# MINI_SAM_D51_006.net
KiCad netlist of a schematic drawn in EAGLE
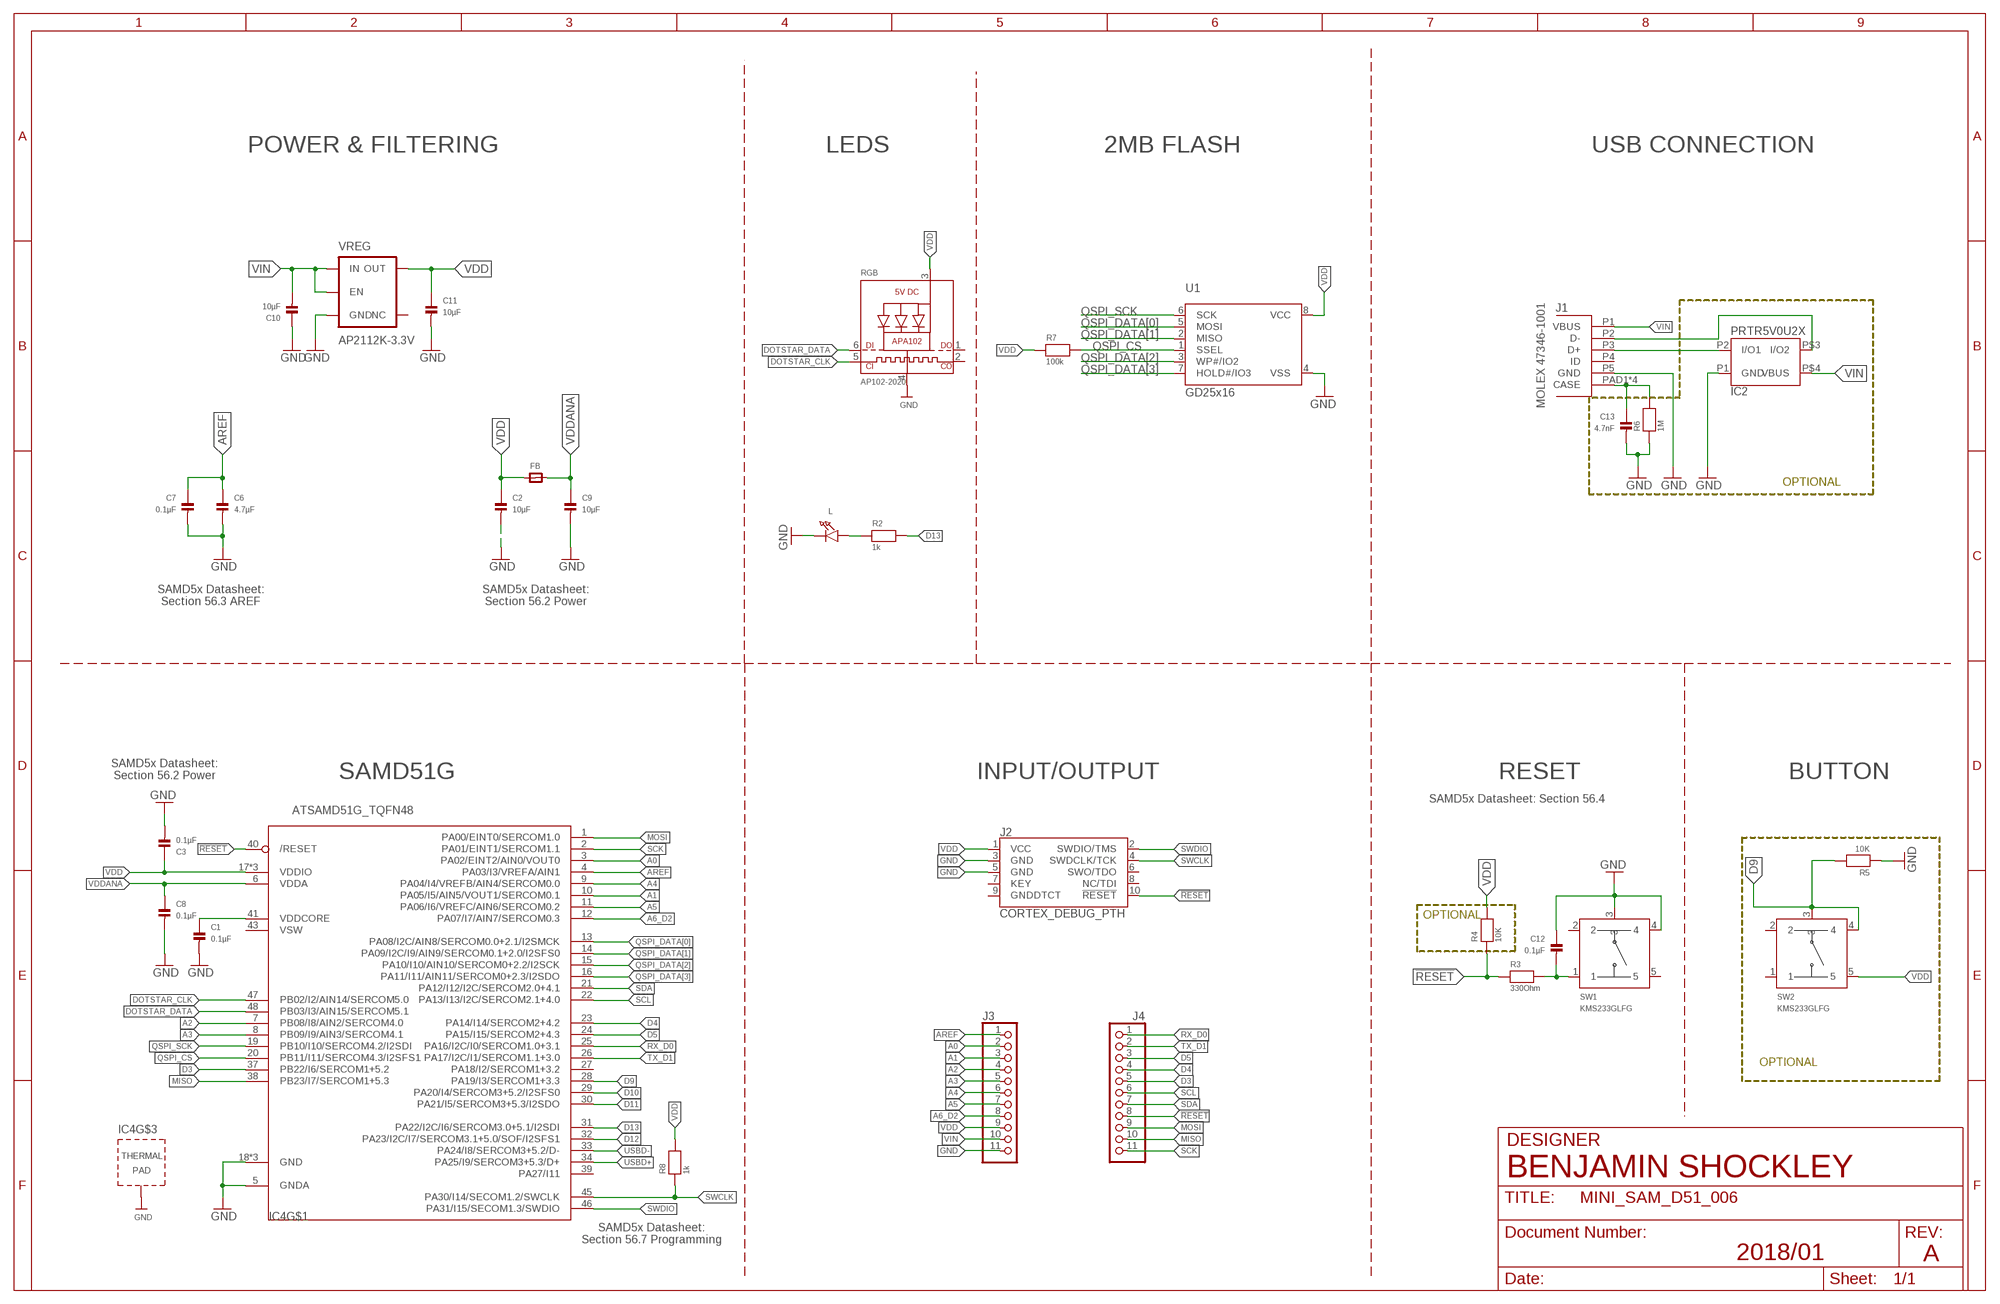
[diagram p0: schematic, sheet 1]

(export (version "E")
  (design (tool "Eeschema 10.0.6"))
  (components
    (comp (ref "C1")
      (value "0.1µF")
      (footprint "eagle-import:_0603MP")
      (libsource (lib "eagle-import") (part "CAP_CERAMIC_0603MP"))
    )
    (comp (ref "C2")
      (value "10µF")
      (footprint "eagle-import:_0603MP")
      (libsource (lib "eagle-import") (part "CAP_CERAMIC_0603MP"))
    )
    (comp (ref "C3")
      (value "0.1µF")
      (footprint "eagle-import:_0603MP")
      (libsource (lib "eagle-import") (part "CAP_CERAMIC_0603MP"))
    )
    (comp (ref "C6")
      (value "4.7µF")
      (footprint "eagle-import:_0603MP")
      (libsource (lib "eagle-import") (part "CAP_CERAMIC_0603MP"))
    )
    (comp (ref "C7")
      (value "0.1µF")
      (footprint "eagle-import:_0603MP")
      (libsource (lib "eagle-import") (part "CAP_CERAMIC_0603MP"))
    )
    (comp (ref "C8")
      (value "0.1µF")
      (footprint "eagle-import:_0603MP")
      (libsource (lib "eagle-import") (part "CAP_CERAMIC_0603MP"))
    )
    (comp (ref "C9")
      (value "10µF")
      (footprint "eagle-import:_0603MP")
      (libsource (lib "eagle-import") (part "CAP_CERAMIC_0603MP"))
    )
    (comp (ref "C10")
      (value "10µF")
      (footprint "eagle-import:_0603MP")
      (libsource (lib "eagle-import") (part "CAP_CERAMIC_0603MP"))
    )
    (comp (ref "C11")
      (value "10µF")
      (footprint "eagle-import:_0603MP")
      (libsource (lib "eagle-import") (part "CAP_CERAMIC_0603MP"))
    )
    (comp (ref "C12")
      (value "0.1µF")
      (footprint "eagle-import:_0603MP")
      (libsource (lib "eagle-import") (part "CAP_CERAMIC_0603MP"))
    )
    (comp (ref "C13")
      (value "4.7nF")
      (footprint "eagle-import:_0603MP")
      (libsource (lib "eagle-import") (part "CAP_CERAMIC_0603MP"))
    )
    (comp (ref "FB")
      (value "FERRITE_0603MP")
      (footprint "eagle-import:_0603MP")
      (libsource (lib "eagle-import") (part "FERRITE_0603MP"))
    )
    (comp (ref "IC2")
      (value "PRTR5V0U2X")
      (footprint "eagle-import:SOT143B_REFLOW")
      (libsource (lib "eagle-import") (part "PRTR5V0U2X"))
    )
    (comp (ref "IC4")
      (value "ATSAMD51G_TQFN48")
      (footprint "eagle-import:TQFN48_7MM")
      (libsource (lib "eagle-import") (part "ATSAMD51G_TQFN48"))
    )
    (comp (ref "J1")
      (value "MOLEX_47346-100147346")
      (footprint "eagle-import:MOLEX_47346-1001")
      (libsource (lib "eagle-import") (part "MOLEX_47346-100147346"))
    )
    (comp (ref "J2")
      (value "CORTEX_DEBUG_PTH")
      (footprint "eagle-import:2X5-PTH-1.27MM")
      (libsource (lib "eagle-import") (part "CORTEX_DEBUG_PTH"))
    )
    (comp (ref "J3")
      (value "PINHD-1X111X11_SMT")
      (footprint "eagle-import:1X11_SMT")
      (libsource (lib "eagle-import") (part "PINHD-1X111X11_SMT"))
    )
    (comp (ref "J4")
      (value "PINHD-1X111X11_SMT")
      (footprint "eagle-import:1X11_SMT")
      (libsource (lib "eagle-import") (part "PINHD-1X111X11_SMT"))
    )
    (comp (ref "L")
      (value "LED0603_NOOUTLINE")
      (footprint "eagle-import:CHIPLED_0603_NOOUTLINE")
      (libsource (lib "eagle-import") (part "LED0603_NOOUTLINE"))
    )
    (comp (ref "R2")
      (value "1k")
      (footprint "eagle-import:_0603MP")
      (libsource (lib "eagle-import") (part "RESISTOR_0603MP"))
    )
    (comp (ref "R3")
      (value "330Ohm")
      (footprint "eagle-import:_0603MP")
      (libsource (lib "eagle-import") (part "RESISTOR_0603MP"))
    )
    (comp (ref "R4")
      (value "10K")
      (footprint "eagle-import:_0603MP")
      (libsource (lib "eagle-import") (part "RESISTOR_0603MP"))
    )
    (comp (ref "R5")
      (value "10K")
      (footprint "eagle-import:_0603MP")
      (libsource (lib "eagle-import") (part "RESISTOR_0603MP"))
    )
    (comp (ref "R6")
      (value "1M")
      (footprint "eagle-import:_0603MP")
      (libsource (lib "eagle-import") (part "RESISTOR_0603MP"))
    )
    (comp (ref "R7")
      (value "100k")
      (footprint "eagle-import:_0603MP")
      (libsource (lib "eagle-import") (part "RESISTOR_0603MP"))
    )
    (comp (ref "R8")
      (value "1k")
      (footprint "eagle-import:_0603MP")
      (libsource (lib "eagle-import") (part "RESISTOR_0603MP"))
    )
    (comp (ref "RGB")
      (value "AP102-2020")
      (footprint "eagle-import:APA102_2020")
      (libsource (lib "eagle-import") (part "APA1022020"))
    )
    (comp (ref "SW1")
      (value "KMS233GLFG")
      (footprint "eagle-import:KMS_SWITCH")
      (libsource (lib "eagle-import") (part "KMS_SWITCHKMS"))
    )
    (comp (ref "SW2")
      (value "KMS233GLFG")
      (footprint "eagle-import:KMS_SWITCH")
      (libsource (lib "eagle-import") (part "KMS_SWITCHKMS"))
    )
    (comp (ref "U1")
      (value "GD25x16")
      (footprint "eagle-import:USON8")
      (libsource (lib "eagle-import") (part "SPIFLASH_8PINUX"))
    )
    (comp (ref "VREG")
      (value "AP2112K-3.3V")
      (footprint "eagle-import:SOT23-5")
      (libsource (lib "eagle-import") (part "V_REG_AP2112K-3.3V"))
    )
  )
  (nets
    (net (code "1") (name "/VSW") (class "Default")
      (node (ref "IC4") (pin "43") (pinfunction "VSW_43") (pintype "power_in"))
    )
    (net (code "2") (name "/~{RESET}") (class "Default")
      (node (ref "IC4") (pin "40") (pinfunction "/RESET_40") (pintype "bidirectional"))
      (node (ref "J2") (pin "10") (pinfunction "~{RESET}_10") (pintype "bidirectional"))
      (node (ref "J4") (pin "8") (pinfunction "8_8") (pintype "passive"))
      (node (ref "R3") (pin "1") (pinfunction "1_1") (pintype "passive"))
      (node (ref "R4") (pin "1") (pinfunction "1_1") (pintype "passive"))
    )
    (net (code "3") (name "A0") (class "Default")
      (node (ref "IC4") (pin "3") (pinfunction "PA02/EINT2/AIN0/VOUT0_3") (pintype "bidirectional"))
      (node (ref "J3") (pin "2") (pinfunction "2_2") (pintype "passive"))
    )
    (net (code "4") (name "A1") (class "Default")
      (node (ref "IC4") (pin "10") (pinfunction "PA05/I5/AIN5/VOUT1/SERCOM0.1_10") (pintype "bidirectional"))
      (node (ref "J3") (pin "3") (pinfunction "3_3") (pintype "passive"))
    )
    (net (code "5") (name "A2") (class "Default")
      (node (ref "IC4") (pin "7") (pinfunction "PB08/I8/AIN2/SERCOM4.0_7") (pintype "bidirectional"))
      (node (ref "J3") (pin "4") (pinfunction "4_4") (pintype "passive"))
    )
    (net (code "6") (name "A3") (class "Default")
      (node (ref "IC4") (pin "8") (pinfunction "PB09/I9/AIN3/SERCOM4.1_8") (pintype "bidirectional"))
      (node (ref "J3") (pin "5") (pinfunction "5_5") (pintype "passive"))
    )
    (net (code "7") (name "A4") (class "Default")
      (node (ref "IC4") (pin "9") (pinfunction "PA04/I4/VREFB/AIN4/SERCOM0.0_9") (pintype "bidirectional"))
      (node (ref "J3") (pin "6") (pinfunction "6_6") (pintype "passive"))
    )
    (net (code "8") (name "A5") (class "Default")
      (node (ref "IC4") (pin "11") (pinfunction "PA06/I6/VREFC/AIN6/SERCOM0.2_11") (pintype "bidirectional"))
      (node (ref "J3") (pin "7") (pinfunction "7_7") (pintype "passive"))
    )
    (net (code "9") (name "A6_D2") (class "Default")
      (node (ref "IC4") (pin "12") (pinfunction "PA07/I7/AIN7/SERCOM0.3_12") (pintype "bidirectional"))
      (node (ref "J3") (pin "8") (pinfunction "8_8") (pintype "passive"))
    )
    (net (code "10") (name "AREF") (class "Default")
      (node (ref "C6") (pin "1") (pinfunction "P$1_1") (pintype "passive"))
      (node (ref "C7") (pin "1") (pinfunction "P$1_1") (pintype "passive"))
      (node (ref "IC4") (pin "4") (pinfunction "PA03/I3/VREFA/AIN1_4") (pintype "bidirectional"))
      (node (ref "J3") (pin "1") (pinfunction "1_1") (pintype "passive"))
    )
    (net (code "11") (name "D3") (class "Default")
      (node (ref "IC4") (pin "37") (pinfunction "PB22/I6/SERCOM1+5.2_37") (pintype "bidirectional"))
      (node (ref "J4") (pin "5") (pinfunction "5_5") (pintype "passive"))
    )
    (net (code "12") (name "D4") (class "Default")
      (node (ref "IC4") (pin "23") (pinfunction "PA14/I14/SERCOM2+4.2_23") (pintype "bidirectional"))
      (node (ref "J4") (pin "4") (pinfunction "4_4") (pintype "passive"))
    )
    (net (code "13") (name "D5") (class "Default")
      (node (ref "IC4") (pin "24") (pinfunction "PA15/I15/SERCOM2+4.3_24") (pintype "bidirectional"))
      (node (ref "J4") (pin "3") (pinfunction "3_3") (pintype "passive"))
    )
    (net (code "14") (name "D9") (class "Default")
      (node (ref "IC4") (pin "28") (pinfunction "PA19/I3/SERCOM1+3.3_28") (pintype "bidirectional"))
      (node (ref "R5") (pin "2") (pinfunction "2_2") (pintype "passive"))
      (node (ref "SW2") (pin "3") (pinfunction "3_3") (pintype "bidirectional"))
      (node (ref "SW2") (pin "4") (pinfunction "4_4") (pintype "bidirectional"))
    )
    (net (code "15") (name "D10") (class "Default")
      (node (ref "IC4") (pin "29") (pinfunction "PA20/I4/SERCOM3+5.2/I2SFS0_29") (pintype "bidirectional"))
    )
    (net (code "16") (name "D11") (class "Default")
      (node (ref "IC4") (pin "30") (pinfunction "PA21/I5/SERCOM3+5.3/I2SDO_30") (pintype "bidirectional"))
    )
    (net (code "17") (name "D12") (class "Default")
      (node (ref "IC4") (pin "32") (pinfunction "PA23/I2C/I7/SERCOM3.1+5.0/SOF/I2SFS1_32") (pintype "bidirectional"))
    )
    (net (code "18") (name "D13") (class "Default")
      (node (ref "IC4") (pin "31") (pinfunction "PA22/I2C/I6/SERCOM3.0+5.1/I2SDI_31") (pintype "bidirectional"))
      (node (ref "R2") (pin "2") (pinfunction "2_2") (pintype "passive"))
    )
    (net (code "19") (name "DOTSTAR_CLK") (class "Default")
      (node (ref "IC4") (pin "47") (pinfunction "PB02/I2/AIN14/SERCOM5.0_47") (pintype "bidirectional"))
      (node (ref "RGB") (pin "5") (pinfunction "CKI_5") (pintype "input"))
    )
    (net (code "20") (name "DOTSTAR_DATA") (class "Default")
      (node (ref "IC4") (pin "48") (pinfunction "PB03/I3/AIN15/SERCOM5.1_48") (pintype "bidirectional"))
      (node (ref "RGB") (pin "6") (pinfunction "DI_6") (pintype "input"))
    )
    (net (code "21") (name "GND") (class "Default")
      (node (ref "C1") (pin "2") (pinfunction "P$2_2") (pintype "passive"))
      (node (ref "C10") (pin "1") (pinfunction "P$1_1") (pintype "passive"))
      (node (ref "C11") (pin "2") (pinfunction "P$2_2") (pintype "passive"))
      (node (ref "C12") (pin "1") (pinfunction "P$1_1") (pintype "passive"))
      (node (ref "C13") (pin "2") (pinfunction "P$2_2") (pintype "passive"))
      (node (ref "C2") (pin "2") (pinfunction "P$2_2") (pintype "passive"))
      (node (ref "C3") (pin "2") (pinfunction "P$2_2") (pintype "passive"))
      (node (ref "C6") (pin "2") (pinfunction "P$2_2") (pintype "passive"))
      (node (ref "C7") (pin "2") (pinfunction "P$2_2") (pintype "passive"))
      (node (ref "C8") (pin "2") (pinfunction "P$2_2") (pintype "passive"))
      (node (ref "C9") (pin "2") (pinfunction "P$2_2") (pintype "passive"))
      (node (ref "IC2") (pin "P1") (pinfunction "GND_P1") (pintype "bidirectional"))
      (node (ref "IC4") (pin "18") (pinfunction "GND_18") (pintype "power_in"))
      (node (ref "IC4") (pin "35") (pinfunction "GND_35") (pintype "power_in"))
      (node (ref "IC4") (pin "42") (pinfunction "GND_42") (pintype "power_in"))
      (node (ref "IC4") (pin "5") (pinfunction "GNDA_5") (pintype "power_in"))
      (node (ref "IC4") (pin "THERMAL") (pinfunction "TP_THERMAL") (pintype "power_in"))
      (node (ref "J1") (pin "P5") (pinfunction "GND_P5") (pintype "power_in"))
      (node (ref "J2") (pin "3") (pinfunction "GND_3") (pintype "bidirectional"))
      (node (ref "J2") (pin "5") (pinfunction "GND_5") (pintype "bidirectional"))
      (node (ref "J3") (pin "11") (pinfunction "11_11") (pintype "passive"))
      (node (ref "L") (pin "C") (pinfunction "C_C") (pintype "passive"))
      (node (ref "R5") (pin "1") (pinfunction "1_1") (pintype "passive"))
      (node (ref "R6") (pin "1") (pinfunction "1_1") (pintype "passive"))
      (node (ref "RGB") (pin "4") (pinfunction "GND_4") (pintype "power_in"))
      (node (ref "SW1") (pin "3") (pinfunction "3_3") (pintype "bidirectional"))
      (node (ref "SW1") (pin "4") (pinfunction "4_4") (pintype "bidirectional"))
      (node (ref "U1") (pin "4") (pinfunction "VSS_4") (pintype "bidirectional"))
      (node (ref "VREG") (pin "2") (pinfunction "GND_2") (pintype "input"))
    )
    (net (code "22") (name "MISO") (class "Default")
      (node (ref "IC4") (pin "38") (pinfunction "PB23/I7/SERCOM1+5.3_38") (pintype "bidirectional"))
      (node (ref "J4") (pin "10") (pinfunction "10_10") (pintype "passive"))
    )
    (net (code "23") (name "MOSI") (class "Default")
      (node (ref "IC4") (pin "1") (pinfunction "PA00/EINT0/SERCOM1.0_1") (pintype "bidirectional"))
      (node (ref "J4") (pin "9") (pinfunction "9_9") (pintype "passive"))
    )
    (net (code "24") (name "Net-(C1-P$1)") (class "Default")
      (node (ref "C1") (pin "1") (pinfunction "P$1_1") (pintype "passive"))
      (node (ref "IC4") (pin "41") (pinfunction "VDDCORE_41") (pintype "power_in"))
    )
    (net (code "25") (name "Net-(C12-P$2)") (class "Default")
      (node (ref "C12") (pin "2") (pinfunction "P$2_2") (pintype "passive"))
      (node (ref "R3") (pin "2") (pinfunction "2_2") (pintype "passive"))
      (node (ref "SW1") (pin "1") (pinfunction "1_1") (pintype "bidirectional"))
    )
    (net (code "26") (name "Net-(C13-P$1)") (class "Default")
      (node (ref "C13") (pin "1") (pinfunction "P$1_1") (pintype "passive"))
      (node (ref "J1") (pin "PAD1") (pinfunction "CASE_PAD1") (pintype "bidirectional"))
      (node (ref "J1") (pin "PAD2") (pinfunction "CASE_PAD2") (pintype "bidirectional"))
      (node (ref "J1") (pin "PAD3") (pinfunction "CASE_PAD3") (pintype "bidirectional"))
      (node (ref "J1") (pin "PAD4") (pinfunction "CASE_PAD4") (pintype "bidirectional"))
      (node (ref "R6") (pin "2") (pinfunction "2_2") (pintype "passive"))
    )
    (net (code "27") (name "Net-(L-PadA)") (class "Default")
      (node (ref "L") (pin "A") (pinfunction "A_A") (pintype "passive"))
      (node (ref "R2") (pin "1") (pinfunction "1_1") (pintype "passive"))
    )
    (net (code "28") (name "QSPI_CS") (class "Default")
      (node (ref "IC4") (pin "20") (pinfunction "PB11/I11/SERCOM4.3/I2SFS1_20") (pintype "bidirectional"))
      (node (ref "R7") (pin "2") (pinfunction "2_2") (pintype "passive"))
      (node (ref "U1") (pin "1") (pinfunction "SSEL_1") (pintype "bidirectional"))
    )
    (net (code "29") (name "QSPI_DATA[0]") (class "Default")
      (node (ref "IC4") (pin "13") (pinfunction "PA08/I2C/AIN8/SERCOM0.0+2.1/I2SMCK_13") (pintype "bidirectional"))
      (node (ref "U1") (pin "5") (pinfunction "MOSI_5") (pintype "bidirectional"))
    )
    (net (code "30") (name "QSPI_DATA[1]") (class "Default")
      (node (ref "IC4") (pin "14") (pinfunction "PA09/I2C/I9/AIN9/SERCOM0.1+2.0/I2SFS0_14") (pintype "bidirectional"))
      (node (ref "U1") (pin "2") (pinfunction "MISO_2") (pintype "bidirectional"))
    )
    (net (code "31") (name "QSPI_DATA[2]") (class "Default")
      (node (ref "IC4") (pin "15") (pinfunction "PA10/I10/AIN10/SERCOM0+2.2/I2SCK_15") (pintype "bidirectional"))
      (node (ref "U1") (pin "3") (pinfunction "WP#/IO2_3") (pintype "bidirectional"))
    )
    (net (code "32") (name "QSPI_DATA[3]") (class "Default")
      (node (ref "IC4") (pin "16") (pinfunction "PA11/I11/AIN11/SERCOM0+2.3/I2SDO_16") (pintype "bidirectional"))
      (node (ref "U1") (pin "7") (pinfunction "HOLD#/IO3_7") (pintype "bidirectional"))
    )
    (net (code "33") (name "QSPI_SCK") (class "Default")
      (node (ref "IC4") (pin "19") (pinfunction "PB10/I10/SERCOM4.2/I2SDI_19") (pintype "bidirectional"))
      (node (ref "U1") (pin "6") (pinfunction "SCK_6") (pintype "bidirectional"))
    )
    (net (code "34") (name "RX_D0") (class "Default")
      (node (ref "IC4") (pin "25") (pinfunction "PA16/I2C/I0/SERCOM1.0+3.1_25") (pintype "bidirectional"))
      (node (ref "J4") (pin "1") (pinfunction "1_1") (pintype "passive"))
    )
    (net (code "35") (name "SCK") (class "Default")
      (node (ref "IC4") (pin "2") (pinfunction "PA01/EINT1/SERCOM1.1_2") (pintype "bidirectional"))
      (node (ref "J4") (pin "11") (pinfunction "11_11") (pintype "passive"))
    )
    (net (code "36") (name "SCL") (class "Default")
      (node (ref "IC4") (pin "22") (pinfunction "PA13/I13/I2C/SERCOM2.1+4.0_22") (pintype "bidirectional"))
      (node (ref "J4") (pin "6") (pinfunction "6_6") (pintype "passive"))
    )
    (net (code "37") (name "SDA") (class "Default")
      (node (ref "IC4") (pin "21") (pinfunction "PA12/I12/I2C/SERCOM2.0+4.1_21") (pintype "bidirectional"))
      (node (ref "J4") (pin "7") (pinfunction "7_7") (pintype "passive"))
    )
    (net (code "38") (name "SWCLK") (class "Default")
      (node (ref "IC4") (pin "45") (pinfunction "PA30/I14/SECOM1.2/SWCLK_45") (pintype "bidirectional"))
      (node (ref "J2") (pin "4") (pinfunction "SWDCLK/TCK_4") (pintype "bidirectional"))
      (node (ref "R8") (pin "1") (pinfunction "1_1") (pintype "passive"))
    )
    (net (code "39") (name "SWDIO") (class "Default")
      (node (ref "IC4") (pin "46") (pinfunction "PA31/I15/SECOM1.3/SWDIO_46") (pintype "bidirectional"))
      (node (ref "J2") (pin "2") (pinfunction "SWDIO/TMS_2") (pintype "bidirectional"))
    )
    (net (code "40") (name "TX_D1") (class "Default")
      (node (ref "IC4") (pin "26") (pinfunction "PA17/I2C/I1/SERCOM1.1+3.0_26") (pintype "bidirectional"))
      (node (ref "J4") (pin "2") (pinfunction "2_2") (pintype "passive"))
    )
    (net (code "41") (name "USBD+") (class "Default")
      (node (ref "IC2") (pin "P2") (pinfunction "I/O1_P2") (pintype "bidirectional"))
      (node (ref "IC4") (pin "34") (pinfunction "PA25/I9/SERCOM3+5.3/D+_34") (pintype "bidirectional"))
      (node (ref "J1") (pin "P3") (pinfunction "D+_P3") (pintype "bidirectional"))
    )
    (net (code "42") (name "USBD-") (class "Default")
      (node (ref "IC2") (pin "P$3") (pinfunction "I/O2_P$3") (pintype "bidirectional"))
      (node (ref "IC4") (pin "33") (pinfunction "PA24/I8/SERCOM3+5.2/D-_33") (pintype "bidirectional"))
      (node (ref "J1") (pin "P2") (pinfunction "D-_P2") (pintype "bidirectional"))
    )
    (net (code "43") (name "VDD") (class "Default")
      (node (ref "C11") (pin "1") (pinfunction "P$1_1") (pintype "passive"))
      (node (ref "C2") (pin "1") (pinfunction "P$1_1") (pintype "passive"))
      (node (ref "C3") (pin "1") (pinfunction "P$1_1") (pintype "passive"))
      (node (ref "FB") (pin "1") (pinfunction "P$1_1") (pintype "passive"))
      (node (ref "IC4") (pin "17") (pinfunction "VDDIO_17") (pintype "power_in"))
      (node (ref "IC4") (pin "36") (pinfunction "VDDIO_36") (pintype "power_in"))
      (node (ref "IC4") (pin "44") (pinfunction "VDDIO_44") (pintype "power_in"))
      (node (ref "J2") (pin "1") (pinfunction "VCC_1") (pintype "bidirectional"))
      (node (ref "J3") (pin "9") (pinfunction "9_9") (pintype "passive"))
      (node (ref "R4") (pin "2") (pinfunction "2_2") (pintype "passive"))
      (node (ref "R7") (pin "1") (pinfunction "1_1") (pintype "passive"))
      (node (ref "R8") (pin "2") (pinfunction "2_2") (pintype "passive"))
      (node (ref "RGB") (pin "3") (pinfunction "VDD_3") (pintype "power_in"))
      (node (ref "SW2") (pin "5") (pinfunction "5_5") (pintype "bidirectional"))
      (node (ref "U1") (pin "8") (pinfunction "VCC_8") (pintype "bidirectional"))
      (node (ref "VREG") (pin "5") (pinfunction "OUT_5") (pintype "passive"))
    )
    (net (code "44") (name "VDDANA") (class "Default")
      (node (ref "C8") (pin "1") (pinfunction "P$1_1") (pintype "passive"))
      (node (ref "C9") (pin "1") (pinfunction "P$1_1") (pintype "passive"))
      (node (ref "FB") (pin "2") (pinfunction "P$2_2") (pintype "passive"))
      (node (ref "IC4") (pin "6") (pinfunction "VDDA_6") (pintype "power_in"))
    )
    (net (code "45") (name "VIN") (class "Default")
      (node (ref "C10") (pin "2") (pinfunction "P$2_2") (pintype "passive"))
      (node (ref "IC2") (pin "P$4") (pinfunction "VBUS_P$4") (pintype "bidirectional"))
      (node (ref "J1") (pin "P1") (pinfunction "VBUS_P1") (pintype "power_in"))
      (node (ref "J3") (pin "10") (pinfunction "10_10") (pintype "passive"))
      (node (ref "VREG") (pin "1") (pinfunction "IN_1") (pintype "input"))
      (node (ref "VREG") (pin "3") (pinfunction "EN_3") (pintype "input"))
    )
    (net (code "46") (name "unconnected-(IC4A-PA18{slash}I2{slash}SERCOM1+3.2-Pad27)") (class "Default")
      (node (ref "IC4") (pin "27") (pinfunction "PA18/I2/SERCOM1+3.2_27") (pintype "bidirectional"))
    )
    (net (code "47") (name "unconnected-(IC4A-PA27{slash}I11-Pad39)") (class "Default")
      (node (ref "IC4") (pin "39") (pinfunction "PA27/I11_39") (pintype "bidirectional"))
    )
    (net (code "48") (name "unconnected-(J1-ID-PadP4)") (class "Default")
      (node (ref "J1") (pin "P4") (pinfunction "ID_P4") (pintype "bidirectional"))
    )
    (net (code "49") (name "unconnected-(J2-GNDDTCT-Pad9)") (class "Default")
      (node (ref "J2") (pin "9") (pinfunction "GNDDTCT_9") (pintype "bidirectional"))
    )
    (net (code "50") (name "unconnected-(J2-KEY-Pad7)") (class "Default")
      (node (ref "J2") (pin "7") (pinfunction "KEY_7") (pintype "bidirectional"))
    )
    (net (code "51") (name "unconnected-(J2-NC{slash}TDI-Pad8)") (class "Default")
      (node (ref "J2") (pin "8") (pinfunction "NC/TDI_8") (pintype "bidirectional"))
    )
    (net (code "52") (name "unconnected-(J2-SWO{slash}TDO-Pad6)") (class "Default")
      (node (ref "J2") (pin "6") (pinfunction "SWO/TDO_6") (pintype "bidirectional"))
    )
    (net (code "53") (name "unconnected-(RGB-CKO-Pad2)") (class "Default")
      (node (ref "RGB") (pin "2") (pinfunction "CKO_2") (pintype "output"))
    )
    (net (code "54") (name "unconnected-(RGB-DO-Pad1)") (class "Default")
      (node (ref "RGB") (pin "1") (pinfunction "DO_1") (pintype "output"))
    )
    (net (code "55") (name "unconnected-(SW1-Pad2)") (class "Default")
      (node (ref "SW1") (pin "2") (pinfunction "2_2") (pintype "bidirectional"))
    )
    (net (code "56") (name "unconnected-(SW1-Pad5)") (class "Default")
      (node (ref "SW1") (pin "5") (pinfunction "5_5") (pintype "bidirectional"))
    )
    (net (code "57") (name "unconnected-(SW2-Pad1)") (class "Default")
      (node (ref "SW2") (pin "1") (pinfunction "1_1") (pintype "bidirectional"))
    )
    (net (code "58") (name "unconnected-(SW2-Pad2)") (class "Default")
      (node (ref "SW2") (pin "2") (pinfunction "2_2") (pintype "bidirectional"))
    )
    (net (code "59") (name "unconnected-(VREG-NC-Pad4)") (class "Default")
      (node (ref "VREG") (pin "4") (pinfunction "NC_4") (pintype "input"))
    )
  )
)
